# controller.net
KiCad netlist of a schematic drawn in Altium Designer
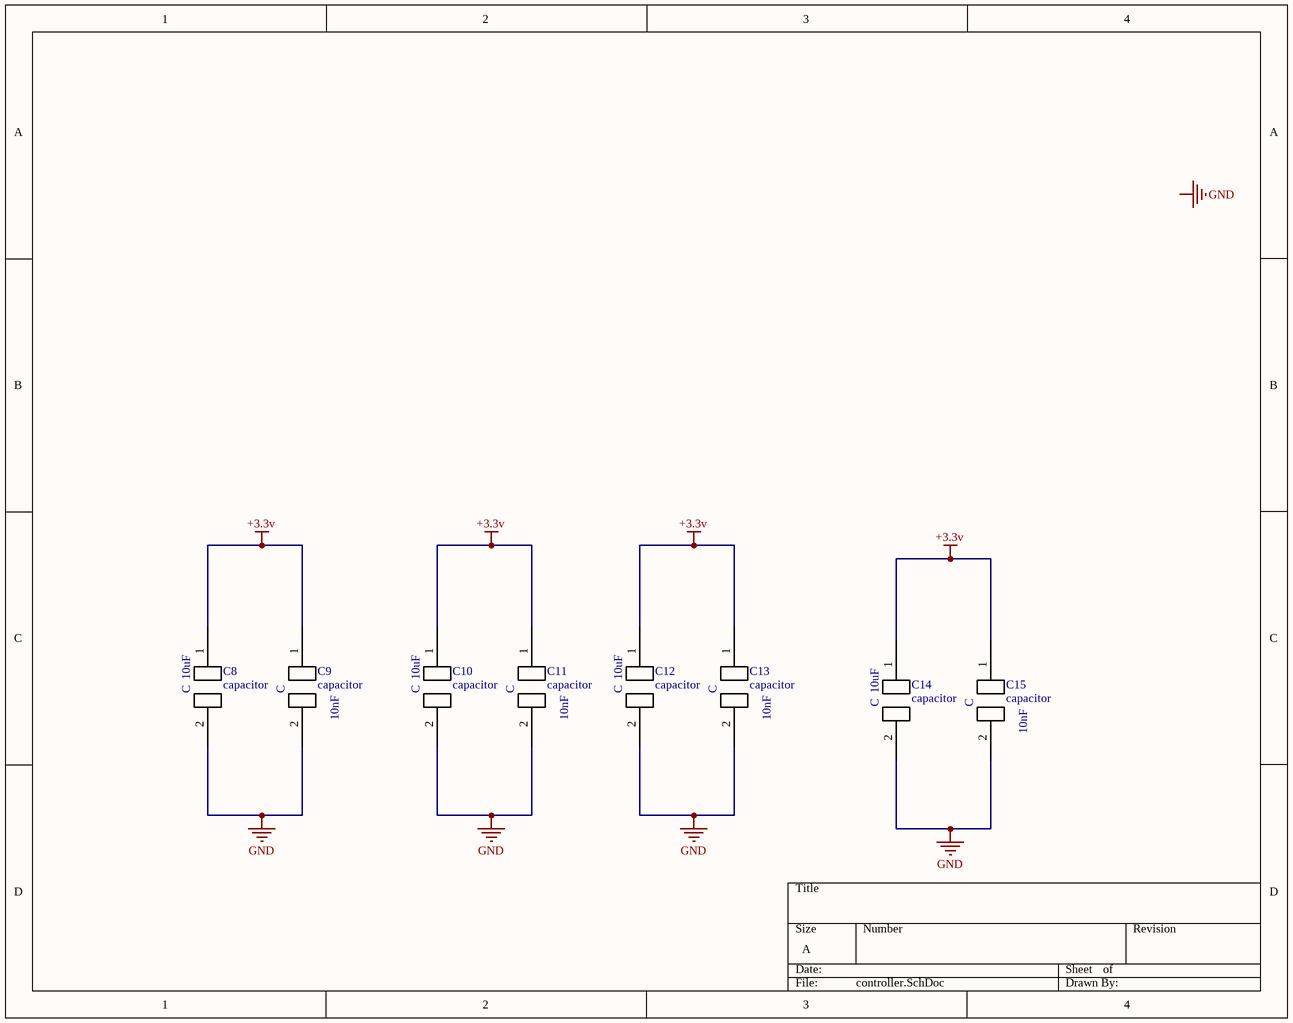
[diagram p0: controller.SchDoc]

(export (version "E")
  (design (tool "Eeschema 10.0.6"))
  (components
    (comp (ref "C8")
      (value "capacitor")
      (footprint "0603")
      (fields (field (name "ALTIUM_UNNAMED_1") "10uF"))
      (libsource (lib "pasives") (part "capacitor"))
    )
    (comp (ref "C9")
      (value "capacitor")
      (footprint "0603")
      (fields (field (name "ALTIUM_UNNAMED_1") "10nF"))
      (libsource (lib "pasives") (part "capacitor"))
    )
    (comp (ref "C10")
      (value "capacitor")
      (footprint "0603")
      (fields (field (name "ALTIUM_UNNAMED_1") "10uF"))
      (libsource (lib "pasives") (part "capacitor"))
    )
    (comp (ref "C11")
      (value "capacitor")
      (footprint "0603")
      (fields (field (name "ALTIUM_UNNAMED_1") "10nF"))
      (libsource (lib "pasives") (part "capacitor"))
    )
    (comp (ref "C12")
      (value "capacitor")
      (footprint "0603")
      (fields (field (name "ALTIUM_UNNAMED_1") "10uF"))
      (libsource (lib "pasives") (part "capacitor"))
    )
    (comp (ref "C13")
      (value "capacitor")
      (footprint "0603")
      (fields (field (name "ALTIUM_UNNAMED_1") "10nF"))
      (libsource (lib "pasives") (part "capacitor"))
    )
    (comp (ref "C14")
      (value "capacitor")
      (footprint "0603")
      (fields (field (name "ALTIUM_UNNAMED_1") "10uF"))
      (libsource (lib "pasives") (part "capacitor"))
    )
    (comp (ref "C15")
      (value "capacitor")
      (footprint "0603")
      (fields (field (name "ALTIUM_UNNAMED_1") "10nF"))
      (libsource (lib "pasives") (part "capacitor"))
    )
  )
  (nets
    (net (code "1") (name "+3.3v") (class "Default")
      (node (ref "C10") (pin "1") (pinfunction "1_1") (pintype "passive"))
      (node (ref "C11") (pin "1") (pinfunction "1_1") (pintype "passive"))
      (node (ref "C12") (pin "1") (pinfunction "1_1") (pintype "passive"))
      (node (ref "C13") (pin "1") (pinfunction "1_1") (pintype "passive"))
      (node (ref "C14") (pin "1") (pinfunction "1_1") (pintype "passive"))
      (node (ref "C15") (pin "1") (pinfunction "1_1") (pintype "passive"))
      (node (ref "C8") (pin "1") (pinfunction "1_1") (pintype "passive"))
      (node (ref "C9") (pin "1") (pinfunction "1_1") (pintype "passive"))
    )
    (net (code "2") (name "GND") (class "Default")
      (node (ref "C10") (pin "2") (pinfunction "2_2") (pintype "passive"))
      (node (ref "C11") (pin "2") (pinfunction "2_2") (pintype "passive"))
      (node (ref "C12") (pin "2") (pinfunction "2_2") (pintype "passive"))
      (node (ref "C13") (pin "2") (pinfunction "2_2") (pintype "passive"))
      (node (ref "C14") (pin "2") (pinfunction "2_2") (pintype "passive"))
      (node (ref "C15") (pin "2") (pinfunction "2_2") (pintype "passive"))
      (node (ref "C8") (pin "2") (pinfunction "2_2") (pintype "passive"))
      (node (ref "C9") (pin "2") (pinfunction "2_2") (pintype "passive"))
    )
  )
)
